# MICRO_AND_VREF.net
KiCad netlist of a schematic drawn in Altium Designer
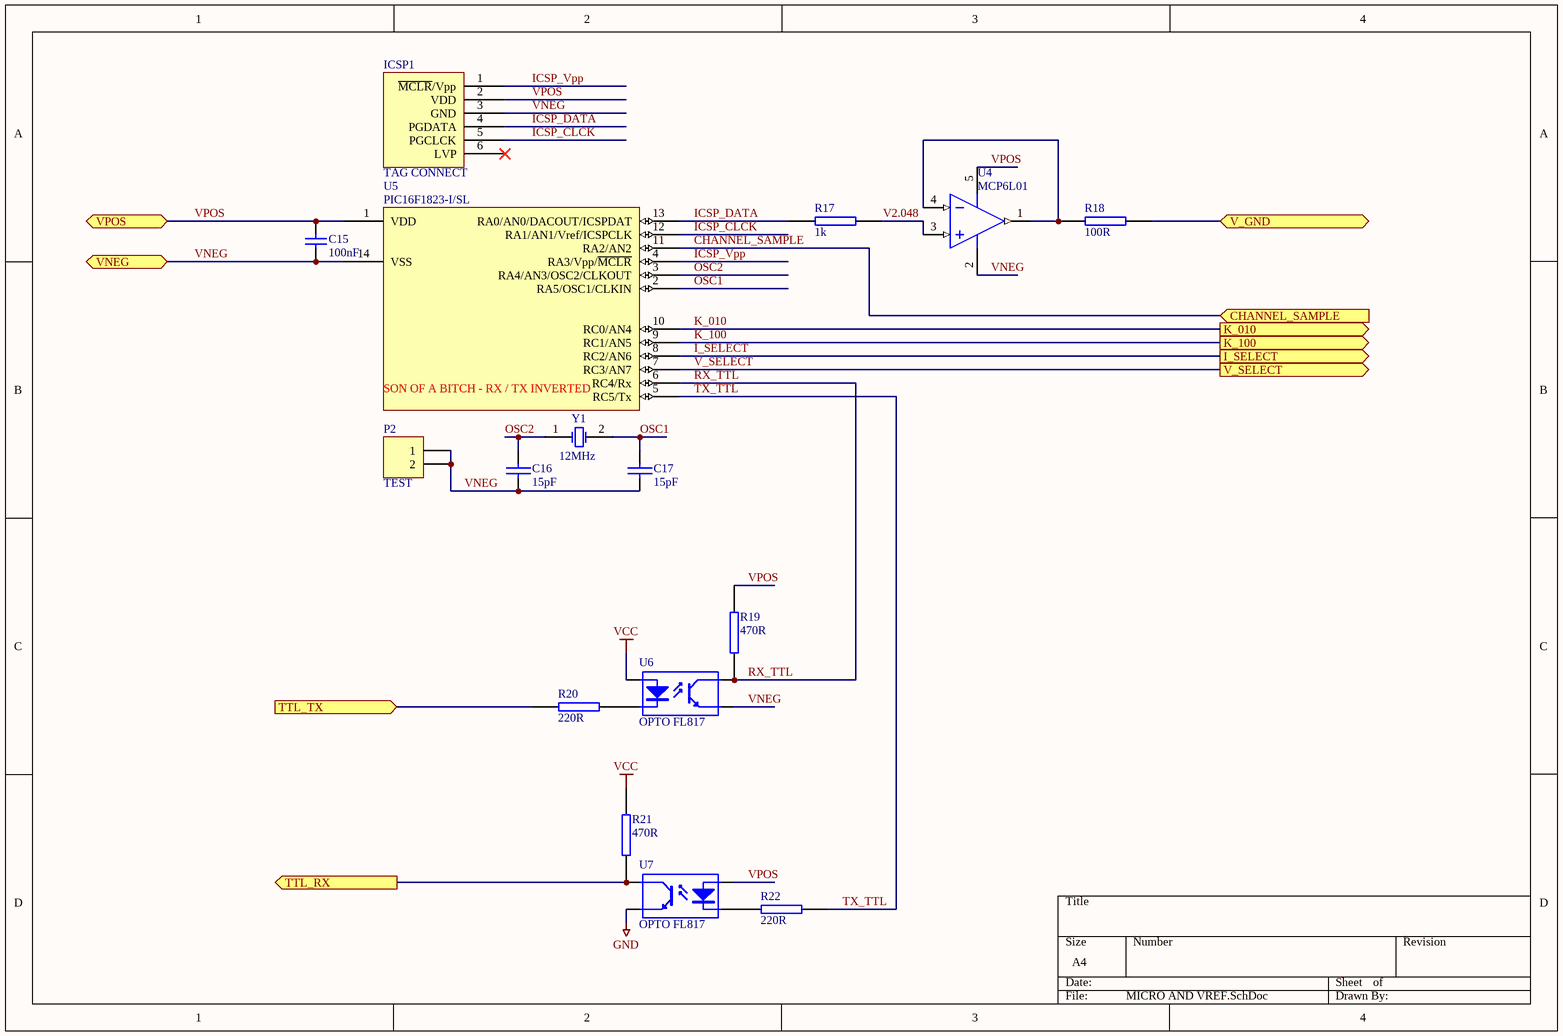
[diagram p0: MICRO AND VREF.SchDoc]

(export (version "E")
  (design (tool "Eeschema 10.0.6"))
  (components
    (comp (ref "C15")
      (value "100nF")
      (footprint "CAP (3D) - 0603")
      (description "Capacitor")
      (libsource (lib "Miscellaneous Devices") (part "Cap"))
    )
    (comp (ref "C16")
      (value "15pF")
      (footprint "CAP (3D) - 0603")
      (description "CAPACITOR SMD 0402")
      (fields (field (name "MOUSER PART NO.") "140-CC504N150J-RC") (field (name "MANUFACTURER") "Xicon"))
      (libsource (lib "401 CCPA") (part "CAP"))
    )
    (comp (ref "C17")
      (value "15pF")
      (footprint "CAP (3D) - 0603")
      (description "CAPACITOR SMD 0402")
      (fields (field (name "MOUSER PART NO.") "140-CC504N150J-RC") (field (name "MANUFACTURER") "Xicon"))
      (libsource (lib "401 CCPA") (part "CAP"))
    )
    (comp (ref "ICSP1")
      (value "TAG CONNECT")
      (footprint "ICSP - TAG CONNECT TYPE2")
      (fields (field (name "MANUFACTURER") "N/A - PCB ARTWORK"))
      (libsource (lib "I2C PENDANT") (part "ICSP - TAG CONNECT"))
    )
    (comp (ref "P2")
      (value "TEST")
      (footprint "HDR1X2")
      (description "Header, 2-Pin")
      (fields
        (field (name "MANUFACTURER") "Bourns")
        (field (name "MANUFACTURER PART NO.") "CR0603-FX-5900ELF")
      )
      (libsource (lib "Miscellaneous Connectors") (part "Header 2"))
    )
    (comp (ref "R17")
      (value "1k")
      (footprint "RES (3D) - 0603")
      (description "RESISTOR SMD 0603 1k")
      (libsource (lib "NASCO Resistors") (part "RES SMD 0603 1k"))
    )
    (comp (ref "R18")
      (value "100R")
      (footprint "RES (3D) - 0603")
      (description "RESISTOR SMD 0603")
      (libsource (lib "NASCO") (part "RES SMD 0603"))
    )
    (comp (ref "R19")
      (value "470R")
      (footprint "RES (3D) - 0603")
      (description "RESISTOR SMD 0603")
      (libsource (lib "NASCO Resistors") (part "RES SMD 0603 100R"))
    )
    (comp (ref "R20")
      (value "220R")
      (footprint "RES (3D) - 0603")
      (description "RESISTOR SMD 0603 1k")
      (libsource (lib "NASCO Resistors") (part "RES SMD 0603 1k"))
    )
    (comp (ref "R21")
      (value "470R")
      (footprint "RES (3D) - 0603")
      (description "RESISTOR SMD 0603")
      (libsource (lib "NASCO Resistors") (part "RES SMD 0603 100R"))
    )
    (comp (ref "R22")
      (value "220R")
      (footprint "RES (3D) - 0603")
      (description "RESISTOR SMD 0603 1k")
      (libsource (lib "NASCO Resistors") (part "RES SMD 0603 1k"))
    )
    (comp (ref "U4") (value "MCP6L01") (footprint "SOT23-5AL") (libsource (lib "Schlib1") (part "MCP6L01")))
    (comp (ref "U5")
      (value "PIC16F1823-I/SL")
      (footprint "SOIC-14")
      (libsource (lib "*") (part "PIC16F1823"))
    )
    (comp (ref "U6")
      (value "OPTO FL817")
      (footprint "DIP_4")
      (description "4-Pin Phototransistor Optocoupler")
      (libsource (lib "Schlib1") (part "FL817"))
    )
    (comp (ref "U7")
      (value "OPTO FL817")
      (footprint "DIP_4")
      (description "4-Pin Phototransistor Optocoupler")
      (libsource (lib "Schlib1") (part "FL817"))
    )
    (comp (ref "Y1")
      (value "12MHz")
      (footprint "CRYSTAL 3x8")
      (description "Crystal Oscillator")
      (fields (field (name "Comment") "XTAL"))
      (libsource (lib "Miscellaneous Devices") (part "XTAL"))
    )
  )
  (nets
    (net (code "1") (name "/CHANNEL_SAMPLE") (class "Default")
      (node (ref "U5") (pin "11") (pinfunction "RA2/AN2_11") (pintype "bidirectional"))
    )
    (net (code "2") (name "/ICSP_CLCK") (class "Default")
      (node (ref "ICSP1") (pin "5") (pinfunction "PGCLCK_5") (pintype "passive"))
      (node (ref "U5") (pin "12") (pinfunction "RA1/AN1/Vref/ICSPCLK_12") (pintype "bidirectional"))
    )
    (net (code "3") (name "/ICSP_DATA") (class "Default")
      (node (ref "ICSP1") (pin "4") (pinfunction "PGDATA_4") (pintype "passive"))
      (node (ref "R17") (pin "2") (pinfunction "2_2") (pintype "passive"))
      (node (ref "U5") (pin "13") (pinfunction "RA0/AN0/DACOUT/ICSPDAT_13") (pintype "bidirectional"))
    )
    (net (code "4") (name "/ICSP_Vpp") (class "Default")
      (node (ref "ICSP1") (pin "1") (pinfunction "~{MCLR}/Vpp_1") (pintype "passive"))
      (node (ref "U5") (pin "4") (pinfunction "RA3/Vpp/~{MCLR}_4") (pintype "bidirectional"))
    )
    (net (code "5") (name "/I_SELECT") (class "Default")
      (node (ref "U5") (pin "8") (pinfunction "RC2/AN6_8") (pintype "bidirectional"))
    )
    (net (code "6") (name "/K_010") (class "Default")
      (node (ref "U5") (pin "10") (pinfunction "RC0/AN4_10") (pintype "bidirectional"))
    )
    (net (code "7") (name "/K_100") (class "Default")
      (node (ref "U5") (pin "9") (pinfunction "RC1/AN5_9") (pintype "bidirectional"))
    )
    (net (code "8") (name "/OSC1") (class "Default")
      (node (ref "C17") (pin "1") (pinfunction "1_1") (pintype "passive"))
      (node (ref "U5") (pin "2") (pinfunction "RA5/OSC1/CLKIN_2") (pintype "bidirectional"))
      (node (ref "Y1") (pin "2") (pinfunction "OSC2_2") (pintype "passive"))
    )
    (net (code "9") (name "/OSC2") (class "Default")
      (node (ref "C16") (pin "1") (pinfunction "1_1") (pintype "passive"))
      (node (ref "U5") (pin "3") (pinfunction "RA4/AN3/OSC2/CLKOUT_3") (pintype "bidirectional"))
      (node (ref "Y1") (pin "1") (pinfunction "OSC1_1") (pintype "passive"))
    )
    (net (code "10") (name "/RX_TTL") (class "Default")
      (node (ref "R19") (pin "2") (pinfunction "2_2") (pintype "passive"))
      (node (ref "U5") (pin "6") (pinfunction "RC4/Rx_6") (pintype "bidirectional"))
      (node (ref "U6") (pin "4") (pinfunction "C_4") (pintype "passive"))
    )
    (net (code "11") (name "/TTL_RX") (class "Default")
      (node (ref "R21") (pin "2") (pinfunction "2_2") (pintype "passive"))
      (node (ref "U7") (pin "4") (pinfunction "C_4") (pintype "passive"))
    )
    (net (code "12") (name "/TTL_TX") (class "Default")
      (node (ref "R20") (pin "1") (pinfunction "1_1") (pintype "passive"))
    )
    (net (code "13") (name "/TX_TTL") (class "Default")
      (node (ref "R22") (pin "2") (pinfunction "2_2") (pintype "passive"))
      (node (ref "U5") (pin "5") (pinfunction "RC5/Tx_5") (pintype "bidirectional"))
    )
    (net (code "14") (name "/V2.048") (class "Default")
      (node (ref "R17") (pin "1") (pinfunction "1_1") (pintype "passive"))
      (node (ref "U4") (pin "3") (pinfunction "INA+_3") (pintype "input"))
    )
    (net (code "15") (name "/VNEG") (class "Default")
      (node (ref "C15") (pin "1") (pinfunction "1_1") (pintype "passive"))
      (node (ref "C16") (pin "2") (pinfunction "2_2") (pintype "passive"))
      (node (ref "C17") (pin "2") (pinfunction "2_2") (pintype "passive"))
      (node (ref "ICSP1") (pin "3") (pinfunction "GND_3") (pintype "passive"))
      (node (ref "P2") (pin "1") (pinfunction "1_1") (pintype "passive"))
      (node (ref "P2") (pin "2") (pinfunction "2_2") (pintype "passive"))
      (node (ref "U4") (pin "2") (pinfunction "GND_2") (pintype "power_in"))
      (node (ref "U5") (pin "14") (pinfunction "VSS_14") (pintype "power_in"))
      (node (ref "U6") (pin "3") (pinfunction "E_3") (pintype "passive"))
    )
    (net (code "16") (name "/VPOS") (class "Default")
      (node (ref "C15") (pin "2") (pinfunction "2_2") (pintype "passive"))
      (node (ref "ICSP1") (pin "2") (pinfunction "VDD_2") (pintype "passive"))
      (node (ref "R19") (pin "1") (pinfunction "1_1") (pintype "passive"))
      (node (ref "U4") (pin "5") (pinfunction "V+_5") (pintype "power_in"))
      (node (ref "U5") (pin "1") (pinfunction "VDD_1") (pintype "power_in"))
      (node (ref "U7") (pin "1") (pinfunction "A_1") (pintype "passive"))
    )
    (net (code "17") (name "/V_GND") (class "Default")
      (node (ref "R18") (pin "2") (pinfunction "2_2") (pintype "passive"))
    )
    (net (code "18") (name "/V_SELECT") (class "Default")
      (node (ref "U5") (pin "7") (pinfunction "RC3/AN7_7") (pintype "bidirectional"))
    )
    (net (code "19") (name "GND") (class "Default")
      (node (ref "U7") (pin "3") (pinfunction "E_3") (pintype "passive"))
    )
    (net (code "20") (name "Net-(U4-INA-)") (class "Default")
      (node (ref "R18") (pin "1") (pinfunction "1_1") (pintype "passive"))
      (node (ref "U4") (pin "1") (pinfunction "OUTA_1") (pintype "output"))
      (node (ref "U4") (pin "4") (pinfunction "INA-_4") (pintype "input"))
    )
    (net (code "21") (name "Net-(U6-K)") (class "Default")
      (node (ref "R20") (pin "2") (pinfunction "2_2") (pintype "passive"))
      (node (ref "U6") (pin "2") (pinfunction "K_2") (pintype "passive"))
    )
    (net (code "22") (name "Net-(U7-K)") (class "Default")
      (node (ref "R22") (pin "1") (pinfunction "1_1") (pintype "passive"))
      (node (ref "U7") (pin "2") (pinfunction "K_2") (pintype "passive"))
    )
    (net (code "23") (name "VCC") (class "Default")
      (node (ref "R21") (pin "1") (pinfunction "1_1") (pintype "passive"))
      (node (ref "U6") (pin "1") (pinfunction "A_1") (pintype "passive"))
    )
    (net (code "24") (name "unconnected-(ICSP1-LVP-Pad6)") (class "Default")
      (node (ref "ICSP1") (pin "6") (pinfunction "LVP_6") (pintype "passive+no_connect"))
    )
  )
)
